# BNSK_Authoring_Light.net
KiCad netlist of a schematic drawn in EAGLE
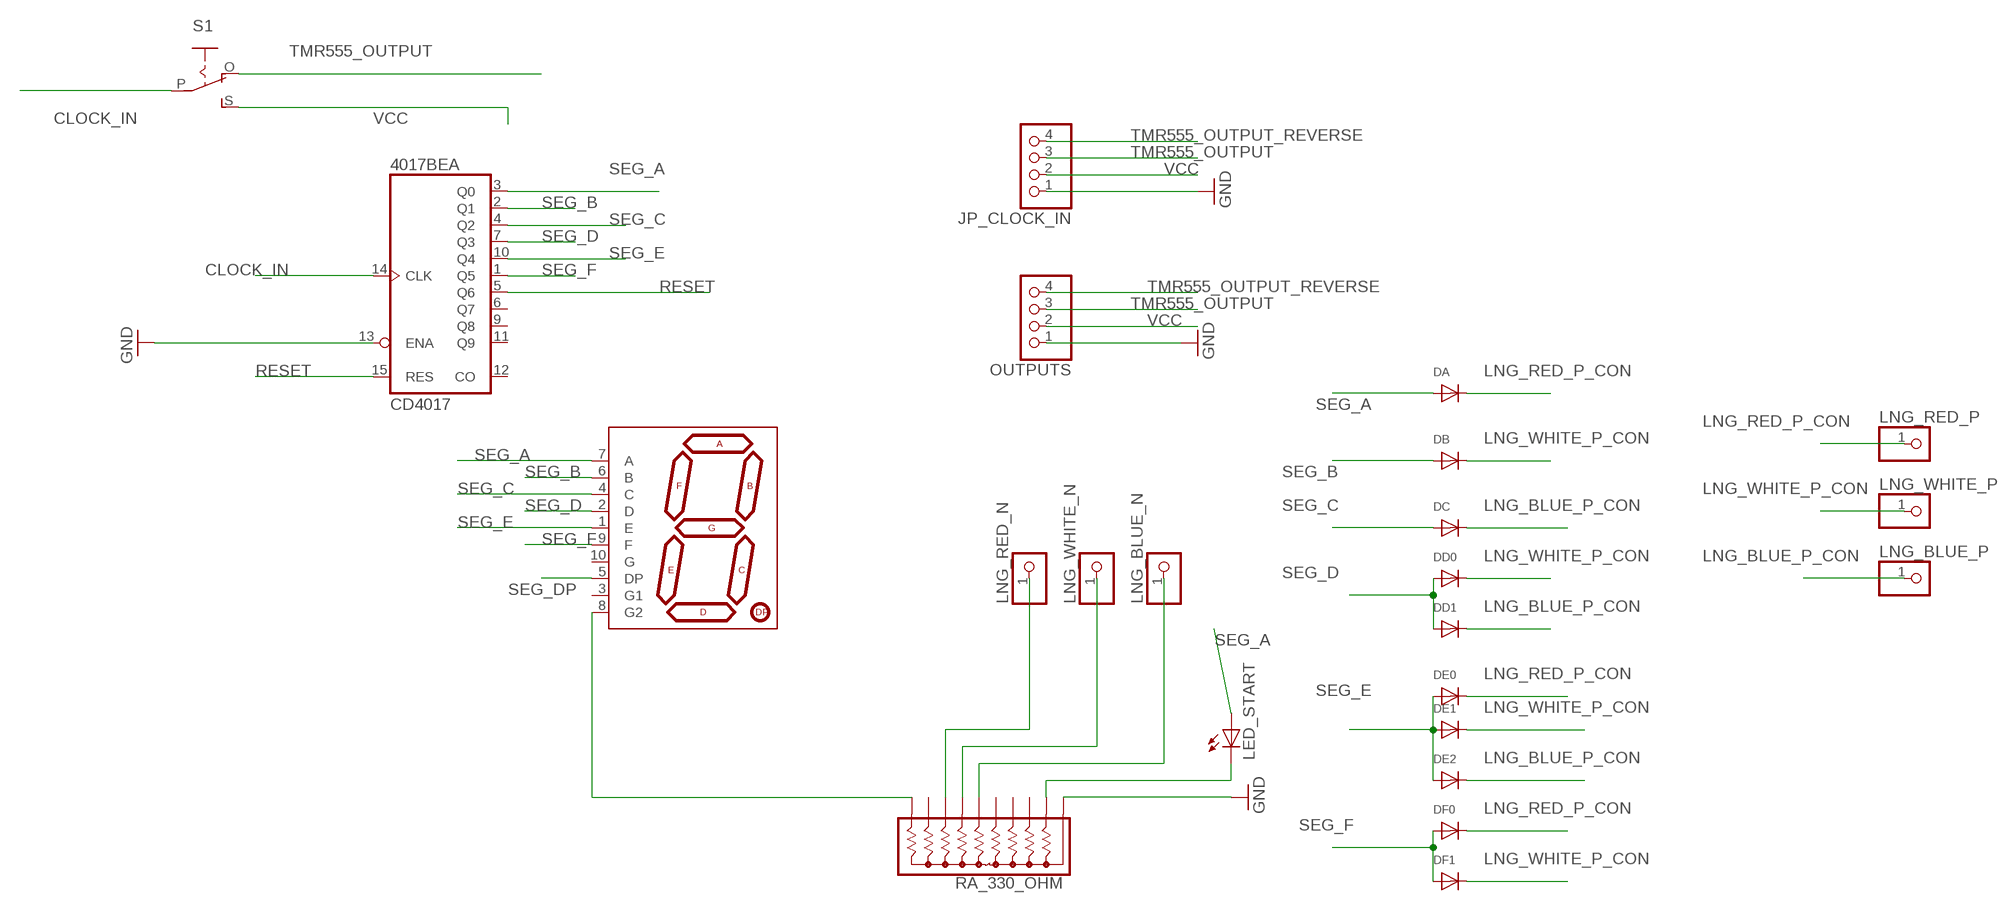
[diagram p0: schematic, sheet 1]

(export (version "E")
  (design (tool "Eeschema 10.0.6"))
  (components
    (comp (ref "4017BE")
      (value "CD4017")
      (footprint "eagle-import:DIL16")
      (libsource (lib "eagle-import") (part "CD4017"))
    )
    (comp (ref "DA")
      (value "DIODESMA")
      (footprint "eagle-import:SMADIODE")
      (libsource (lib "eagle-import") (part "DIODESMA"))
    )
    (comp (ref "DB")
      (value "DIODESMA")
      (footprint "eagle-import:SMADIODE")
      (libsource (lib "eagle-import") (part "DIODESMA"))
    )
    (comp (ref "DC")
      (value "DIODESMA")
      (footprint "eagle-import:SMADIODE")
      (libsource (lib "eagle-import") (part "DIODESMA"))
    )
    (comp (ref "DD0")
      (value "DIODESMA")
      (footprint "eagle-import:SMADIODE")
      (libsource (lib "eagle-import") (part "DIODESMA"))
    )
    (comp (ref "DD1")
      (value "DIODESMA")
      (footprint "eagle-import:SMADIODE")
      (libsource (lib "eagle-import") (part "DIODESMA"))
    )
    (comp (ref "DE0")
      (value "DIODESMA")
      (footprint "eagle-import:SMADIODE")
      (libsource (lib "eagle-import") (part "DIODESMA"))
    )
    (comp (ref "DE1")
      (value "DIODESMA")
      (footprint "eagle-import:SMADIODE")
      (libsource (lib "eagle-import") (part "DIODESMA"))
    )
    (comp (ref "DE2")
      (value "DIODESMA")
      (footprint "eagle-import:SMADIODE")
      (libsource (lib "eagle-import") (part "DIODESMA"))
    )
    (comp (ref "DF0")
      (value "DIODESMA")
      (footprint "eagle-import:SMADIODE")
      (libsource (lib "eagle-import") (part "DIODESMA"))
    )
    (comp (ref "DF1")
      (value "DIODESMA")
      (footprint "eagle-import:SMADIODE")
      (libsource (lib "eagle-import") (part "DIODESMA"))
    )
    (comp (ref "JP_CLOCK_IN")
      (value "PINHD-1X4")
      (footprint "eagle-import:1X04")
      (libsource (lib "eagle-import") (part "PINHD-1X4"))
    )
    (comp (ref "LED_START")
      (value "LEDSMT1206")
      (footprint "eagle-import:1206")
      (libsource (lib "eagle-import") (part "LEDSMT1206"))
    )
    (comp (ref "LNG_BLUE_N")
      (value "PINHD-1X1")
      (footprint "eagle-import:1X01")
      (libsource (lib "eagle-import") (part "PINHD-1X1"))
    )
    (comp (ref "LNG_BLUE_P")
      (value "PINHD-1X1")
      (footprint "eagle-import:1X01")
      (libsource (lib "eagle-import") (part "PINHD-1X1"))
    )
    (comp (ref "LNG_RED_N")
      (value "PINHD-1X1")
      (footprint "eagle-import:1X01")
      (libsource (lib "eagle-import") (part "PINHD-1X1"))
    )
    (comp (ref "LNG_RED_P")
      (value "PINHD-1X1")
      (footprint "eagle-import:1X01")
      (libsource (lib "eagle-import") (part "PINHD-1X1"))
    )
    (comp (ref "LNG_WHITE_N")
      (value "PINHD-1X1")
      (footprint "eagle-import:1X01")
      (libsource (lib "eagle-import") (part "PINHD-1X1"))
    )
    (comp (ref "LNG_WHITE_P")
      (value "PINHD-1X1")
      (footprint "eagle-import:1X01")
      (libsource (lib "eagle-import") (part "PINHD-1X1"))
    )
    (comp (ref "OUTPUTS")
      (value "PINHD-1X4")
      (footprint "eagle-import:1X04")
      (libsource (lib "eagle-import") (part "PINHD-1X4"))
    )
    (comp (ref "RA_330_OHM")
      (value "4610X")
      (footprint "eagle-import:SIP10")
      (libsource (lib "eagle-import") (part "4610X"))
    )
    (comp (ref "S1")
      (value "EG1218S")
      (footprint "eagle-import:EG1218")
      (libsource (lib "eagle-import") (part "EG1218S"))
    )
    (comp (ref "U$1")
      (value "7-SEGMENT-DISPLAYPTH")
      (footprint "eagle-import:7-SEGMENT-DISPLAY")
      (libsource (lib "eagle-import") (part "7-SEGMENT-DISPLAYPTH"))
    )
  )
  (nets
    (net (code "1") (name "/CLOCK_IN") (class "Default")
      (node (ref "4017BE") (pin "14") (pinfunction "CLK_14") (pintype "input"))
      (node (ref "S1") (pin "P") (pinfunction "P_P") (pintype "passive"))
    )
    (net (code "2") (name "/LNG_BLUE_P_CON") (class "Default")
      (node (ref "DC") (pin "C") (pinfunction "C_C") (pintype "passive"))
      (node (ref "DD1") (pin "C") (pinfunction "C_C") (pintype "passive"))
      (node (ref "DE2") (pin "C") (pinfunction "C_C") (pintype "passive"))
      (node (ref "LNG_BLUE_P") (pin "1") (pinfunction "1_1") (pintype "passive"))
    )
    (net (code "3") (name "/LNG_RED_P_CON") (class "Default")
      (node (ref "DA") (pin "C") (pinfunction "C_C") (pintype "passive"))
      (node (ref "DE0") (pin "C") (pinfunction "C_C") (pintype "passive"))
      (node (ref "DF0") (pin "C") (pinfunction "C_C") (pintype "passive"))
      (node (ref "LNG_RED_P") (pin "1") (pinfunction "1_1") (pintype "passive"))
    )
    (net (code "4") (name "/LNG_WHITE_P_CON") (class "Default")
      (node (ref "DB") (pin "C") (pinfunction "C_C") (pintype "passive"))
      (node (ref "DD0") (pin "C") (pinfunction "C_C") (pintype "passive"))
      (node (ref "DE1") (pin "C") (pinfunction "C_C") (pintype "passive"))
      (node (ref "DF1") (pin "C") (pinfunction "C_C") (pintype "passive"))
      (node (ref "LNG_WHITE_P") (pin "1") (pinfunction "1_1") (pintype "passive"))
    )
    (net (code "5") (name "/RESET") (class "Default")
      (node (ref "4017BE") (pin "15") (pinfunction "RES_15") (pintype "input"))
      (node (ref "4017BE") (pin "5") (pinfunction "Q6_5") (pintype "output"))
    )
    (net (code "6") (name "/SEG_A") (class "Default")
      (node (ref "4017BE") (pin "3") (pinfunction "Q0_3") (pintype "output"))
      (node (ref "DA") (pin "A") (pinfunction "A_A") (pintype "passive"))
      (node (ref "LED_START") (pin "A") (pinfunction "A_A") (pintype "passive"))
      (node (ref "U$1") (pin "7") (pinfunction "A_7") (pintype "bidirectional"))
    )
    (net (code "7") (name "/SEG_B") (class "Default")
      (node (ref "4017BE") (pin "2") (pinfunction "Q1_2") (pintype "output"))
      (node (ref "DB") (pin "A") (pinfunction "A_A") (pintype "passive"))
      (node (ref "U$1") (pin "6") (pinfunction "B_6") (pintype "bidirectional"))
    )
    (net (code "8") (name "/SEG_C") (class "Default")
      (node (ref "4017BE") (pin "4") (pinfunction "Q2_4") (pintype "output"))
      (node (ref "DC") (pin "A") (pinfunction "A_A") (pintype "passive"))
      (node (ref "U$1") (pin "4") (pinfunction "C_4") (pintype "bidirectional"))
    )
    (net (code "9") (name "/SEG_D") (class "Default")
      (node (ref "4017BE") (pin "7") (pinfunction "Q3_7") (pintype "output"))
      (node (ref "DD0") (pin "A") (pinfunction "A_A") (pintype "passive"))
      (node (ref "DD1") (pin "A") (pinfunction "A_A") (pintype "passive"))
      (node (ref "U$1") (pin "2") (pinfunction "D_2") (pintype "bidirectional"))
    )
    (net (code "10") (name "/SEG_DP") (class "Default")
      (node (ref "U$1") (pin "5") (pinfunction "DP_5") (pintype "bidirectional"))
    )
    (net (code "11") (name "/SEG_E") (class "Default")
      (node (ref "4017BE") (pin "10") (pinfunction "Q4_10") (pintype "output"))
      (node (ref "DE0") (pin "A") (pinfunction "A_A") (pintype "passive"))
      (node (ref "DE1") (pin "A") (pinfunction "A_A") (pintype "passive"))
      (node (ref "DE2") (pin "A") (pinfunction "A_A") (pintype "passive"))
      (node (ref "U$1") (pin "1") (pinfunction "E_1") (pintype "bidirectional"))
    )
    (net (code "12") (name "/SEG_F") (class "Default")
      (node (ref "4017BE") (pin "1") (pinfunction "Q5_1") (pintype "output"))
      (node (ref "DF0") (pin "A") (pinfunction "A_A") (pintype "passive"))
      (node (ref "DF1") (pin "A") (pinfunction "A_A") (pintype "passive"))
      (node (ref "U$1") (pin "9") (pinfunction "F_9") (pintype "bidirectional"))
    )
    (net (code "13") (name "/TMR555_OUTPUT") (class "Default")
      (node (ref "JP_CLOCK_IN") (pin "3") (pinfunction "3_3") (pintype "passive"))
      (node (ref "OUTPUTS") (pin "3") (pinfunction "3_3") (pintype "passive"))
      (node (ref "S1") (pin "O") (pinfunction "O_O") (pintype "passive"))
    )
    (net (code "14") (name "/TMR555_OUTPUT_REVERSE") (class "Default")
      (node (ref "JP_CLOCK_IN") (pin "4") (pinfunction "4_4") (pintype "passive"))
      (node (ref "OUTPUTS") (pin "4") (pinfunction "4_4") (pintype "passive"))
    )
    (net (code "15") (name "/VCC") (class "Default")
      (node (ref "JP_CLOCK_IN") (pin "2") (pinfunction "2_2") (pintype "passive"))
      (node (ref "OUTPUTS") (pin "2") (pinfunction "2_2") (pintype "passive"))
      (node (ref "S1") (pin "S") (pinfunction "S_S") (pintype "passive"))
    )
    (net (code "16") (name "GND") (class "Default")
      (node (ref "4017BE") (pin "13") (pinfunction "ENA_13") (pintype "input"))
      (node (ref "JP_CLOCK_IN") (pin "1") (pinfunction "1_1") (pintype "passive"))
      (node (ref "OUTPUTS") (pin "1") (pinfunction "1_1") (pintype "passive"))
      (node (ref "RA_330_OHM") (pin "1") (pinfunction "1_1") (pintype "passive"))
    )
    (net (code "17") (name "Net-(LED_START-PadC)") (class "Default")
      (node (ref "LED_START") (pin "C") (pinfunction "C_C") (pintype "passive"))
      (node (ref "RA_330_OHM") (pin "2") (pinfunction "2_2") (pintype "passive"))
    )
    (net (code "18") (name "Net-(LNG_BLUE_N-Pad1)") (class "Default")
      (node (ref "LNG_BLUE_N") (pin "1") (pinfunction "1_1") (pintype "passive"))
      (node (ref "RA_330_OHM") (pin "6") (pinfunction "6_6") (pintype "passive"))
    )
    (net (code "19") (name "Net-(LNG_RED_N-Pad1)") (class "Default")
      (node (ref "LNG_RED_N") (pin "1") (pinfunction "1_1") (pintype "passive"))
      (node (ref "RA_330_OHM") (pin "8") (pinfunction "8_8") (pintype "passive"))
    )
    (net (code "20") (name "Net-(LNG_WHITE_N-Pad1)") (class "Default")
      (node (ref "LNG_WHITE_N") (pin "1") (pinfunction "1_1") (pintype "passive"))
      (node (ref "RA_330_OHM") (pin "7") (pinfunction "7_7") (pintype "passive"))
    )
    (net (code "21") (name "Net-(U$1-G2)") (class "Default")
      (node (ref "RA_330_OHM") (pin "10") (pinfunction "10_10") (pintype "passive"))
      (node (ref "U$1") (pin "8") (pinfunction "G2_8") (pintype "bidirectional"))
    )
    (net (code "22") (name "unconnected-(4017BEA-CO-Pad12)") (class "Default")
      (node (ref "4017BE") (pin "12") (pinfunction "CO_12") (pintype "output"))
    )
    (net (code "23") (name "unconnected-(4017BEA-Q7-Pad6)") (class "Default")
      (node (ref "4017BE") (pin "6") (pinfunction "Q7_6") (pintype "output"))
    )
    (net (code "24") (name "unconnected-(4017BEA-Q8-Pad9)") (class "Default")
      (node (ref "4017BE") (pin "9") (pinfunction "Q8_9") (pintype "output"))
    )
    (net (code "25") (name "unconnected-(4017BEA-Q9-Pad11)") (class "Default")
      (node (ref "4017BE") (pin "11") (pinfunction "Q9_11") (pintype "output"))
    )
    (net (code "26") (name "unconnected-(RA_330_OHM-Pad3)") (class "Default")
      (node (ref "RA_330_OHM") (pin "3") (pinfunction "3_3") (pintype "passive"))
    )
    (net (code "27") (name "unconnected-(RA_330_OHM-Pad4)") (class "Default")
      (node (ref "RA_330_OHM") (pin "4") (pinfunction "4_4") (pintype "passive"))
    )
    (net (code "28") (name "unconnected-(RA_330_OHM-Pad5)") (class "Default")
      (node (ref "RA_330_OHM") (pin "5") (pinfunction "5_5") (pintype "passive"))
    )
    (net (code "29") (name "unconnected-(RA_330_OHM-Pad9)") (class "Default")
      (node (ref "RA_330_OHM") (pin "9") (pinfunction "9_9") (pintype "passive"))
    )
    (net (code "30") (name "unconnected-(U$1-G-Pad10)") (class "Default")
      (node (ref "U$1") (pin "10") (pinfunction "G_10") (pintype "bidirectional"))
    )
    (net (code "31") (name "unconnected-(U$1-G1-Pad3)") (class "Default")
      (node (ref "U$1") (pin "3") (pinfunction "G1_3") (pintype "bidirectional"))
    )
  )
)
